# FPGA_POWER.net
KiCad netlist of a schematic drawn in Altium Designer
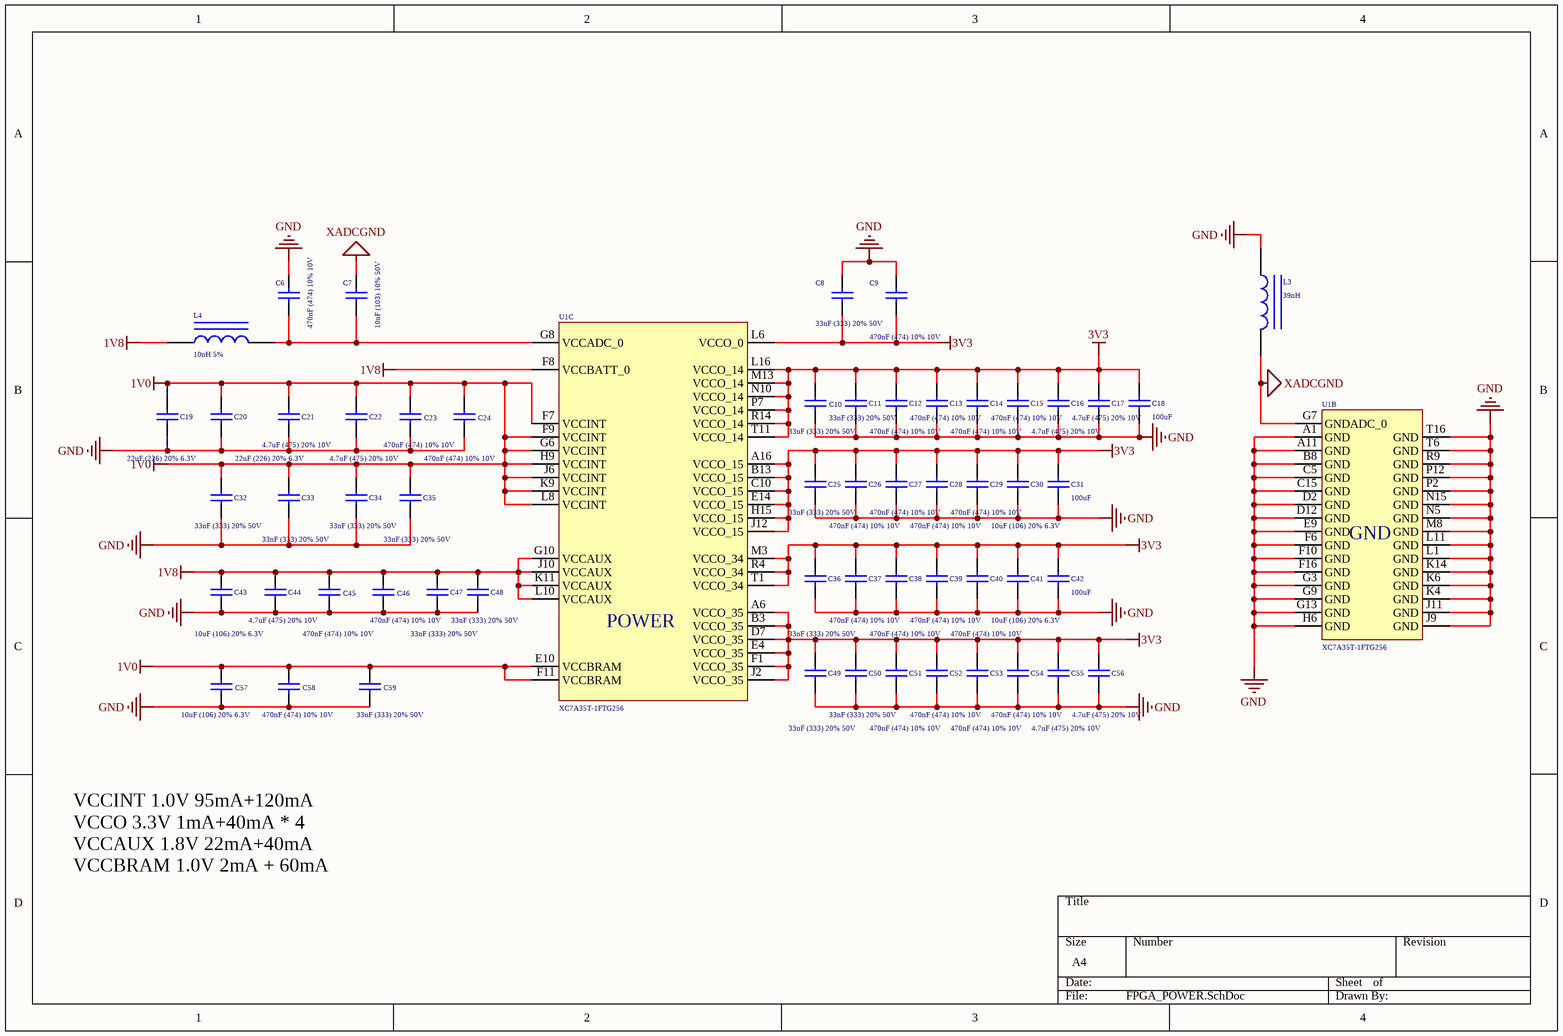
[diagram p0: FPGA_POWER.SchDoc]

(export (version "E")
  (design (tool "Eeschema 10.0.6"))
  (components
    (comp (ref "C6")
      (value "470nF (474) 10% 10V")
      (footprint "0402_C")
      (description "贴片电容")
      (libsource (lib "Cap") (part "0402 470nF (474) 10% 10V"))
    )
    (comp (ref "C7")
      (value "10nF (103) 10% 50V")
      (footprint "0402_C")
      (description "贴片电容")
      (libsource (lib "Cap") (part "0402 10nF (103) 10% 50V"))
    )
    (comp (ref "C8")
      (value "33nF (333) 20% 50V")
      (footprint "0402_C")
      (description "贴片电容")
      (libsource (lib "Cap") (part "0402 33nF (333) 20% 50V"))
    )
    (comp (ref "C9")
      (value "470nF (474) 10% 10V")
      (footprint "0402_C")
      (description "贴片电容")
      (libsource (lib "Cap") (part "0402 470nF (474) 10% 10V"))
    )
    (comp (ref "C10")
      (value "33nF (333) 20% 50V")
      (footprint "0402_C")
      (description "贴片电容")
      (libsource (lib "Cap") (part "0402 33nF (333) 20% 50V"))
    )
    (comp (ref "C11")
      (value "33nF (333) 20% 50V")
      (footprint "0402_C")
      (description "贴片电容")
      (libsource (lib "Cap") (part "0402 33nF (333) 20% 50V"))
    )
    (comp (ref "C12")
      (value "470nF (474) 10% 10V")
      (footprint "0402_C")
      (description "贴片电容")
      (libsource (lib "Cap") (part "0402 470nF (474) 10% 10V"))
    )
    (comp (ref "C13")
      (value "470nF (474) 10% 10V")
      (footprint "0402_C")
      (description "贴片电容")
      (libsource (lib "Cap") (part "0402 470nF (474) 10% 10V"))
    )
    (comp (ref "C14")
      (value "470nF (474) 10% 10V")
      (footprint "0402_C")
      (description "贴片电容")
      (libsource (lib "Cap") (part "0402 470nF (474) 10% 10V"))
    )
    (comp (ref "C15")
      (value "470nF (474) 10% 10V")
      (footprint "0402_C")
      (description "贴片电容")
      (libsource (lib "Cap") (part "0402 470nF (474) 10% 10V"))
    )
    (comp (ref "C16")
      (value "4.7uF (475) 20% 10V")
      (footprint "0402_C")
      (description "贴片电容")
      (libsource (lib "Cap") (part "0402 4.7uF (475) 20% 10V"))
    )
    (comp (ref "C17")
      (value "4.7uF (475) 20% 10V")
      (footprint "0402_C")
      (description "贴片电容")
      (libsource (lib "Cap") (part "0402 4.7uF (475) 20% 10V"))
    )
    (comp (ref "C18")
      (value "100uF")
      (footprint "LC-1206")
      (description "贴片电容")
      (fields (field (name "Comment") "Cap") (field (name "PUBLISHER") "Altium Limited"))
      (libsource (lib "Sparks") (part "Cap"))
    )
    (comp (ref "C19")
      (value "22uF (226) 20% 6.3V")
      (footprint "0603_C")
      (description "贴片电容")
      (libsource (lib "Miscellaneous Devices LC") (part "0603 22uF (226) 20% 6.3V"))
    )
    (comp (ref "C20")
      (value "22uF (226) 20% 6.3V")
      (footprint "0603_C")
      (description "贴片电容")
      (libsource (lib "Miscellaneous Devices LC") (part "0603 22uF (226) 20% 6.3V"))
    )
    (comp (ref "C21")
      (value "4.7uF (475) 20% 10V")
      (footprint "0402_C")
      (description "贴片电容")
      (libsource (lib "Cap") (part "0402 4.7uF (475) 20% 10V"))
    )
    (comp (ref "C22")
      (value "4.7uF (475) 20% 10V")
      (footprint "0402_C")
      (description "贴片电容")
      (libsource (lib "Cap") (part "0402 4.7uF (475) 20% 10V"))
    )
    (comp (ref "C23")
      (value "470nF (474) 10% 10V")
      (footprint "0402_C")
      (description "贴片电容")
      (libsource (lib "Cap") (part "0402 470nF (474) 10% 10V"))
    )
    (comp (ref "C24")
      (value "470nF (474) 10% 10V")
      (footprint "0402_C")
      (description "贴片电容")
      (libsource (lib "Cap") (part "0402 470nF (474) 10% 10V"))
    )
    (comp (ref "C25")
      (value "33nF (333) 20% 50V")
      (footprint "0402_C")
      (description "贴片电容")
      (libsource (lib "Cap") (part "0402 33nF (333) 20% 50V"))
    )
    (comp (ref "C26")
      (value "470nF (474) 10% 10V")
      (footprint "0402_C")
      (description "贴片电容")
      (libsource (lib "Cap") (part "0402 470nF (474) 10% 10V"))
    )
    (comp (ref "C27")
      (value "470nF (474) 10% 10V")
      (footprint "0402_C")
      (description "贴片电容")
      (libsource (lib "Cap") (part "0402 470nF (474) 10% 10V"))
    )
    (comp (ref "C28")
      (value "470nF (474) 10% 10V")
      (footprint "0402_C")
      (description "贴片电容")
      (libsource (lib "Cap") (part "0402 470nF (474) 10% 10V"))
    )
    (comp (ref "C29")
      (value "470nF (474) 10% 10V")
      (footprint "0402_C")
      (description "贴片电容")
      (libsource (lib "Cap") (part "0402 470nF (474) 10% 10V"))
    )
    (comp (ref "C30")
      (value "10uF (106) 20% 6.3V")
      (footprint "0402_C")
      (description "贴片电容")
      (libsource (lib "Cap") (part "0402 10uF (106) 20% 6.3V"))
    )
    (comp (ref "C31")
      (value "100uF")
      (footprint "LC-1206")
      (description "贴片电容")
      (fields (field (name "Comment") "Cap") (field (name "PUBLISHER") "Altium Limited"))
      (libsource (lib "Sparks") (part "Cap"))
    )
    (comp (ref "C32")
      (value "33nF (333) 20% 50V")
      (footprint "0402_C")
      (description "贴片电容")
      (libsource (lib "Cap") (part "0402 33nF (333) 20% 50V"))
    )
    (comp (ref "C33")
      (value "33nF (333) 20% 50V")
      (footprint "0402_C")
      (description "贴片电容")
      (libsource (lib "Cap") (part "0402 33nF (333) 20% 50V"))
    )
    (comp (ref "C34")
      (value "33nF (333) 20% 50V")
      (footprint "0402_C")
      (description "贴片电容")
      (libsource (lib "Cap") (part "0402 33nF (333) 20% 50V"))
    )
    (comp (ref "C35")
      (value "33nF (333) 20% 50V")
      (footprint "0402_C")
      (description "贴片电容")
      (libsource (lib "Cap") (part "0402 33nF (333) 20% 50V"))
    )
    (comp (ref "C36")
      (value "33nF (333) 20% 50V")
      (footprint "0402_C")
      (description "贴片电容")
      (libsource (lib "Cap") (part "0402 33nF (333) 20% 50V"))
    )
    (comp (ref "C37")
      (value "470nF (474) 10% 10V")
      (footprint "0402_C")
      (description "贴片电容")
      (libsource (lib "Cap") (part "0402 470nF (474) 10% 10V"))
    )
    (comp (ref "C38")
      (value "470nF (474) 10% 10V")
      (footprint "0402_C")
      (description "贴片电容")
      (libsource (lib "Cap") (part "0402 470nF (474) 10% 10V"))
    )
    (comp (ref "C39")
      (value "470nF (474) 10% 10V")
      (footprint "0402_C")
      (description "贴片电容")
      (libsource (lib "Cap") (part "0402 470nF (474) 10% 10V"))
    )
    (comp (ref "C40")
      (value "470nF (474) 10% 10V")
      (footprint "0402_C")
      (description "贴片电容")
      (libsource (lib "Cap") (part "0402 470nF (474) 10% 10V"))
    )
    (comp (ref "C41")
      (value "10uF (106) 20% 6.3V")
      (footprint "0402_C")
      (description "贴片电容")
      (libsource (lib "Cap") (part "0402 10uF (106) 20% 6.3V"))
    )
    (comp (ref "C42")
      (value "100uF")
      (footprint "LC-1206")
      (description "贴片电容")
      (fields (field (name "Comment") "Cap") (field (name "PUBLISHER") "Altium Limited"))
      (libsource (lib "Sparks") (part "Cap"))
    )
    (comp (ref "C43")
      (value "10uF (106) 20% 6.3V")
      (footprint "0402_C")
      (description "贴片电容")
      (libsource (lib "Cap") (part "0402 10uF (106) 20% 6.3V"))
    )
    (comp (ref "C44")
      (value "4.7uF (475) 20% 10V")
      (footprint "0402_C")
      (description "贴片电容")
      (libsource (lib "Cap") (part "0402 4.7uF (475) 20% 10V"))
    )
    (comp (ref "C45")
      (value "470nF (474) 10% 10V")
      (footprint "0402_C")
      (description "贴片电容")
      (libsource (lib "Cap") (part "0402 470nF (474) 10% 10V"))
    )
    (comp (ref "C46")
      (value "470nF (474) 10% 10V")
      (footprint "0402_C")
      (description "贴片电容")
      (libsource (lib "Cap") (part "0402 470nF (474) 10% 10V"))
    )
    (comp (ref "C47")
      (value "33nF (333) 20% 50V")
      (footprint "0402_C")
      (description "贴片电容")
      (libsource (lib "Cap") (part "0402 33nF (333) 20% 50V"))
    )
    (comp (ref "C48")
      (value "33nF (333) 20% 50V")
      (footprint "0402_C")
      (description "贴片电容")
      (libsource (lib "Cap") (part "0402 33nF (333) 20% 50V"))
    )
    (comp (ref "C49")
      (value "33nF (333) 20% 50V")
      (footprint "0402_C")
      (description "贴片电容")
      (libsource (lib "Cap") (part "0402 33nF (333) 20% 50V"))
    )
    (comp (ref "C50")
      (value "33nF (333) 20% 50V")
      (footprint "0402_C")
      (description "贴片电容")
      (libsource (lib "Cap") (part "0402 33nF (333) 20% 50V"))
    )
    (comp (ref "C51")
      (value "470nF (474) 10% 10V")
      (footprint "0402_C")
      (description "贴片电容")
      (libsource (lib "Cap") (part "0402 470nF (474) 10% 10V"))
    )
    (comp (ref "C52")
      (value "470nF (474) 10% 10V")
      (footprint "0402_C")
      (description "贴片电容")
      (libsource (lib "Cap") (part "0402 470nF (474) 10% 10V"))
    )
    (comp (ref "C53")
      (value "470nF (474) 10% 10V")
      (footprint "0402_C")
      (description "贴片电容")
      (libsource (lib "Cap") (part "0402 470nF (474) 10% 10V"))
    )
    (comp (ref "C54")
      (value "470nF (474) 10% 10V")
      (footprint "0402_C")
      (description "贴片电容")
      (libsource (lib "Cap") (part "0402 470nF (474) 10% 10V"))
    )
    (comp (ref "C55")
      (value "4.7uF (475) 20% 10V")
      (footprint "0402_C")
      (description "贴片电容")
      (libsource (lib "Cap") (part "0402 4.7uF (475) 20% 10V"))
    )
    (comp (ref "C56")
      (value "4.7uF (475) 20% 10V")
      (footprint "0402_C")
      (description "贴片电容")
      (libsource (lib "Cap") (part "0402 4.7uF (475) 20% 10V"))
    )
    (comp (ref "C57")
      (value "10uF (106) 20% 6.3V")
      (footprint "0402_C")
      (description "贴片电容")
      (libsource (lib "Cap") (part "0402 10uF (106) 20% 6.3V"))
    )
    (comp (ref "C58")
      (value "470nF (474) 10% 10V")
      (footprint "0402_C")
      (description "贴片电容")
      (libsource (lib "Cap") (part "0402 470nF (474) 10% 10V"))
    )
    (comp (ref "C59")
      (value "33nF (333) 20% 50V")
      (footprint "0402_C")
      (description "贴片电容")
      (libsource (lib "Cap") (part "0402 33nF (333) 20% 50V"))
    )
    (comp (ref "L3")
      (value "39nH")
      (footprint "0402_L")
      (description "贴片电感")
      (libsource (lib "IUD") (part "0402 39nH"))
    )
    (comp (ref "L4")
      (value "10nH 5%")
      (footprint "0402_L")
      (description "贴片电感")
      (libsource (lib "IUD") (part "0402 10nH 5%"))
    )
    (comp (ref "U1")
      (value "XC7A35T-1FTG256")
      (footprint "BGA100P9X9-81A")
      (libsource (lib "Schlib") (part "XC7A35T-1FTG256"))
    )
  )
  (nets
    (net (code "1") (name "1V0") (class "Default")
      (node (ref "C19") (pin "2") (pinfunction "2_2") (pintype "passive"))
      (node (ref "C20") (pin "2") (pinfunction "2_2") (pintype "passive"))
      (node (ref "C21") (pin "2") (pinfunction "2_2") (pintype "passive"))
      (node (ref "C22") (pin "2") (pinfunction "2_2") (pintype "passive"))
      (node (ref "C23") (pin "2") (pinfunction "2_2") (pintype "passive"))
      (node (ref "C24") (pin "2") (pinfunction "2_2") (pintype "passive"))
      (node (ref "C32") (pin "2") (pinfunction "2_2") (pintype "passive"))
      (node (ref "C33") (pin "2") (pinfunction "2_2") (pintype "passive"))
      (node (ref "C34") (pin "2") (pinfunction "2_2") (pintype "passive"))
      (node (ref "C35") (pin "2") (pinfunction "2_2") (pintype "passive"))
      (node (ref "C57") (pin "2") (pinfunction "2_2") (pintype "passive"))
      (node (ref "C58") (pin "2") (pinfunction "2_2") (pintype "passive"))
      (node (ref "C59") (pin "2") (pinfunction "2_2") (pintype "passive"))
      (node (ref "U1") (pin "E10") (pinfunction "VCCBRAM_E10") (pintype "passive"))
      (node (ref "U1") (pin "F11") (pinfunction "VCCBRAM_F11") (pintype "passive"))
      (node (ref "U1") (pin "F7") (pinfunction "VCCINT_F7") (pintype "passive"))
      (node (ref "U1") (pin "F9") (pinfunction "VCCINT_F9") (pintype "passive"))
      (node (ref "U1") (pin "G6") (pinfunction "VCCINT_G6") (pintype "passive"))
      (node (ref "U1") (pin "H9") (pinfunction "VCCINT_H9") (pintype "passive"))
      (node (ref "U1") (pin "J6") (pinfunction "VCCINT_J6") (pintype "passive"))
      (node (ref "U1") (pin "K9") (pinfunction "VCCINT_K9") (pintype "passive"))
      (node (ref "U1") (pin "L8") (pinfunction "VCCINT_L8") (pintype "passive"))
    )
    (net (code "2") (name "1V8") (class "Default")
      (node (ref "C43") (pin "2") (pinfunction "2_2") (pintype "passive"))
      (node (ref "C44") (pin "2") (pinfunction "2_2") (pintype "passive"))
      (node (ref "C45") (pin "2") (pinfunction "2_2") (pintype "passive"))
      (node (ref "C46") (pin "2") (pinfunction "2_2") (pintype "passive"))
      (node (ref "C47") (pin "2") (pinfunction "2_2") (pintype "passive"))
      (node (ref "C48") (pin "2") (pinfunction "2_2") (pintype "passive"))
      (node (ref "L4") (pin "1") (pinfunction "1_1") (pintype "passive"))
      (node (ref "U1") (pin "F8") (pinfunction "VCCBATT_0_F8") (pintype "passive"))
      (node (ref "U1") (pin "G10") (pinfunction "VCCAUX_G10") (pintype "passive"))
      (node (ref "U1") (pin "J10") (pinfunction "VCCAUX_J10") (pintype "passive"))
      (node (ref "U1") (pin "K11") (pinfunction "VCCAUX_K11") (pintype "passive"))
      (node (ref "U1") (pin "L10") (pinfunction "VCCAUX_L10") (pintype "passive"))
    )
    (net (code "3") (name "3V3") (class "Default")
      (node (ref "C10") (pin "2") (pinfunction "2_2") (pintype "passive"))
      (node (ref "C11") (pin "2") (pinfunction "2_2") (pintype "passive"))
      (node (ref "C12") (pin "2") (pinfunction "2_2") (pintype "passive"))
      (node (ref "C13") (pin "2") (pinfunction "2_2") (pintype "passive"))
      (node (ref "C14") (pin "2") (pinfunction "2_2") (pintype "passive"))
      (node (ref "C15") (pin "2") (pinfunction "2_2") (pintype "passive"))
      (node (ref "C16") (pin "2") (pinfunction "2_2") (pintype "passive"))
      (node (ref "C17") (pin "2") (pinfunction "2_2") (pintype "passive"))
      (node (ref "C18") (pin "2") (pinfunction "2_2") (pintype "passive"))
      (node (ref "C25") (pin "2") (pinfunction "2_2") (pintype "passive"))
      (node (ref "C26") (pin "2") (pinfunction "2_2") (pintype "passive"))
      (node (ref "C27") (pin "2") (pinfunction "2_2") (pintype "passive"))
      (node (ref "C28") (pin "2") (pinfunction "2_2") (pintype "passive"))
      (node (ref "C29") (pin "2") (pinfunction "2_2") (pintype "passive"))
      (node (ref "C30") (pin "2") (pinfunction "2_2") (pintype "passive"))
      (node (ref "C31") (pin "2") (pinfunction "2_2") (pintype "passive"))
      (node (ref "C36") (pin "2") (pinfunction "2_2") (pintype "passive"))
      (node (ref "C37") (pin "2") (pinfunction "2_2") (pintype "passive"))
      (node (ref "C38") (pin "2") (pinfunction "2_2") (pintype "passive"))
      (node (ref "C39") (pin "2") (pinfunction "2_2") (pintype "passive"))
      (node (ref "C40") (pin "2") (pinfunction "2_2") (pintype "passive"))
      (node (ref "C41") (pin "2") (pinfunction "2_2") (pintype "passive"))
      (node (ref "C42") (pin "2") (pinfunction "2_2") (pintype "passive"))
      (node (ref "C49") (pin "2") (pinfunction "2_2") (pintype "passive"))
      (node (ref "C50") (pin "2") (pinfunction "2_2") (pintype "passive"))
      (node (ref "C51") (pin "2") (pinfunction "2_2") (pintype "passive"))
      (node (ref "C52") (pin "2") (pinfunction "2_2") (pintype "passive"))
      (node (ref "C53") (pin "2") (pinfunction "2_2") (pintype "passive"))
      (node (ref "C54") (pin "2") (pinfunction "2_2") (pintype "passive"))
      (node (ref "C55") (pin "2") (pinfunction "2_2") (pintype "passive"))
      (node (ref "C56") (pin "2") (pinfunction "2_2") (pintype "passive"))
      (node (ref "C8") (pin "1") (pinfunction "1_1") (pintype "passive"))
      (node (ref "C9") (pin "1") (pinfunction "1_1") (pintype "passive"))
      (node (ref "U1") (pin "A16") (pinfunction "VCCO_15_A16") (pintype "passive"))
      (node (ref "U1") (pin "A6") (pinfunction "VCCO_35_A6") (pintype "passive"))
      (node (ref "U1") (pin "B13") (pinfunction "VCCO_15_B13") (pintype "passive"))
      (node (ref "U1") (pin "B3") (pinfunction "VCCO_35_B3") (pintype "passive"))
      (node (ref "U1") (pin "C10") (pinfunction "VCCO_15_C10") (pintype "passive"))
      (node (ref "U1") (pin "D7") (pinfunction "VCCO_35_D7") (pintype "passive"))
      (node (ref "U1") (pin "E14") (pinfunction "VCCO_15_E14") (pintype "passive"))
      (node (ref "U1") (pin "E4") (pinfunction "VCCO_35_E4") (pintype "passive"))
      (node (ref "U1") (pin "F1") (pinfunction "VCCO_35_F1") (pintype "passive"))
      (node (ref "U1") (pin "H15") (pinfunction "VCCO_15_H15") (pintype "passive"))
      (node (ref "U1") (pin "J12") (pinfunction "VCCO_15_J12") (pintype "passive"))
      (node (ref "U1") (pin "J2") (pinfunction "VCCO_35_J2") (pintype "passive"))
      (node (ref "U1") (pin "L16") (pinfunction "VCCO_14_L16") (pintype "passive"))
      (node (ref "U1") (pin "L6") (pinfunction "VCCO_0_L6") (pintype "passive"))
      (node (ref "U1") (pin "M13") (pinfunction "VCCO_14_M13") (pintype "passive"))
      (node (ref "U1") (pin "M3") (pinfunction "VCCO_34_M3") (pintype "passive"))
      (node (ref "U1") (pin "N10") (pinfunction "VCCO_14_N10") (pintype "passive"))
      (node (ref "U1") (pin "P7") (pinfunction "VCCO_14_P7") (pintype "passive"))
      (node (ref "U1") (pin "R14") (pinfunction "VCCO_14_R14") (pintype "passive"))
      (node (ref "U1") (pin "R4") (pinfunction "VCCO_34_R4") (pintype "passive"))
      (node (ref "U1") (pin "T1") (pinfunction "VCCO_34_T1") (pintype "passive"))
      (node (ref "U1") (pin "T11") (pinfunction "VCCO_14_T11") (pintype "passive"))
    )
    (net (code "4") (name "GND") (class "Default")
      (node (ref "C10") (pin "1") (pinfunction "1_1") (pintype "passive"))
      (node (ref "C11") (pin "1") (pinfunction "1_1") (pintype "passive"))
      (node (ref "C12") (pin "1") (pinfunction "1_1") (pintype "passive"))
      (node (ref "C13") (pin "1") (pinfunction "1_1") (pintype "passive"))
      (node (ref "C14") (pin "1") (pinfunction "1_1") (pintype "passive"))
      (node (ref "C15") (pin "1") (pinfunction "1_1") (pintype "passive"))
      (node (ref "C16") (pin "1") (pinfunction "1_1") (pintype "passive"))
      (node (ref "C17") (pin "1") (pinfunction "1_1") (pintype "passive"))
      (node (ref "C18") (pin "1") (pinfunction "1_1") (pintype "passive"))
      (node (ref "C19") (pin "1") (pinfunction "1_1") (pintype "passive"))
      (node (ref "C20") (pin "1") (pinfunction "1_1") (pintype "passive"))
      (node (ref "C21") (pin "1") (pinfunction "1_1") (pintype "passive"))
      (node (ref "C22") (pin "1") (pinfunction "1_1") (pintype "passive"))
      (node (ref "C23") (pin "1") (pinfunction "1_1") (pintype "passive"))
      (node (ref "C24") (pin "1") (pinfunction "1_1") (pintype "passive"))
      (node (ref "C25") (pin "1") (pinfunction "1_1") (pintype "passive"))
      (node (ref "C26") (pin "1") (pinfunction "1_1") (pintype "passive"))
      (node (ref "C27") (pin "1") (pinfunction "1_1") (pintype "passive"))
      (node (ref "C28") (pin "1") (pinfunction "1_1") (pintype "passive"))
      (node (ref "C29") (pin "1") (pinfunction "1_1") (pintype "passive"))
      (node (ref "C30") (pin "1") (pinfunction "1_1") (pintype "passive"))
      (node (ref "C31") (pin "1") (pinfunction "1_1") (pintype "passive"))
      (node (ref "C32") (pin "1") (pinfunction "1_1") (pintype "passive"))
      (node (ref "C33") (pin "1") (pinfunction "1_1") (pintype "passive"))
      (node (ref "C34") (pin "1") (pinfunction "1_1") (pintype "passive"))
      (node (ref "C35") (pin "1") (pinfunction "1_1") (pintype "passive"))
      (node (ref "C36") (pin "1") (pinfunction "1_1") (pintype "passive"))
      (node (ref "C37") (pin "1") (pinfunction "1_1") (pintype "passive"))
      (node (ref "C38") (pin "1") (pinfunction "1_1") (pintype "passive"))
      (node (ref "C39") (pin "1") (pinfunction "1_1") (pintype "passive"))
      (node (ref "C40") (pin "1") (pinfunction "1_1") (pintype "passive"))
      (node (ref "C41") (pin "1") (pinfunction "1_1") (pintype "passive"))
      (node (ref "C42") (pin "1") (pinfunction "1_1") (pintype "passive"))
      (node (ref "C43") (pin "1") (pinfunction "1_1") (pintype "passive"))
      (node (ref "C44") (pin "1") (pinfunction "1_1") (pintype "passive"))
      (node (ref "C45") (pin "1") (pinfunction "1_1") (pintype "passive"))
      (node (ref "C46") (pin "1") (pinfunction "1_1") (pintype "passive"))
      (node (ref "C47") (pin "1") (pinfunction "1_1") (pintype "passive"))
      (node (ref "C48") (pin "1") (pinfunction "1_1") (pintype "passive"))
      (node (ref "C49") (pin "1") (pinfunction "1_1") (pintype "passive"))
      (node (ref "C50") (pin "1") (pinfunction "1_1") (pintype "passive"))
      (node (ref "C51") (pin "1") (pinfunction "1_1") (pintype "passive"))
      (node (ref "C52") (pin "1") (pinfunction "1_1") (pintype "passive"))
      (node (ref "C53") (pin "1") (pinfunction "1_1") (pintype "passive"))
      (node (ref "C54") (pin "1") (pinfunction "1_1") (pintype "passive"))
      (node (ref "C55") (pin "1") (pinfunction "1_1") (pintype "passive"))
      (node (ref "C56") (pin "1") (pinfunction "1_1") (pintype "passive"))
      (node (ref "C57") (pin "1") (pinfunction "1_1") (pintype "passive"))
      (node (ref "C58") (pin "1") (pinfunction "1_1") (pintype "passive"))
      (node (ref "C59") (pin "1") (pinfunction "1_1") (pintype "passive"))
      (node (ref "C6") (pin "2") (pinfunction "2_2") (pintype "passive"))
      (node (ref "C8") (pin "2") (pinfunction "2_2") (pintype "passive"))
      (node (ref "C9") (pin "2") (pinfunction "2_2") (pintype "passive"))
      (node (ref "L3") (pin "1") (pinfunction "1_1") (pintype "passive"))
      (node (ref "U1") (pin "A1") (pinfunction "GND_A1") (pintype "passive"))
      (node (ref "U1") (pin "A11") (pinfunction "GND_A11") (pintype "passive"))
      (node (ref "U1") (pin "B8") (pinfunction "GND_B8") (pintype "passive"))
      (node (ref "U1") (pin "C15") (pinfunction "GND_C15") (pintype "passive"))
      (node (ref "U1") (pin "C5") (pinfunction "GND_C5") (pintype "passive"))
      (node (ref "U1") (pin "D12") (pinfunction "GND_D12") (pintype "passive"))
      (node (ref "U1") (pin "D2") (pinfunction "GND_D2") (pintype "passive"))
      (node (ref "U1") (pin "E9") (pinfunction "GND_E9") (pintype "passive"))
      (node (ref "U1") (pin "F10") (pinfunction "GND_F10") (pintype "passive"))
      (node (ref "U1") (pin "F16") (pinfunction "GND_F16") (pintype "passive"))
      (node (ref "U1") (pin "F6") (pinfunction "GND_F6") (pintype "passive"))
      (node (ref "U1") (pin "G13") (pinfunction "GND_G13") (pintype "passive"))
      (node (ref "U1") (pin "G3") (pinfunction "GND_G3") (pintype "passive"))
      (node (ref "U1") (pin "G9") (pinfunction "GND_G9") (pintype "passive"))
      (node (ref "U1") (pin "H6") (pinfunction "GND_H6") (pintype "passive"))
      (node (ref "U1") (pin "J11") (pinfunction "GND_J11") (pintype "passive"))
      (node (ref "U1") (pin "J9") (pinfunction "GND_J9") (pintype "passive"))
      (node (ref "U1") (pin "K14") (pinfunction "GND_K14") (pintype "passive"))
      (node (ref "U1") (pin "K4") (pinfunction "GND_K4") (pintype "passive"))
      (node (ref "U1") (pin "K6") (pinfunction "GND_K6") (pintype "passive"))
      (node (ref "U1") (pin "L1") (pinfunction "GND_L1") (pintype "passive"))
      (node (ref "U1") (pin "L11") (pinfunction "GND_L11") (pintype "passive"))
      (node (ref "U1") (pin "M8") (pinfunction "GND_M8") (pintype "passive"))
      (node (ref "U1") (pin "N15") (pinfunction "GND_N15") (pintype "passive"))
      (node (ref "U1") (pin "N5") (pinfunction "GND_N5") (pintype "passive"))
      (node (ref "U1") (pin "P12") (pinfunction "GND_P12") (pintype "passive"))
      (node (ref "U1") (pin "P2") (pinfunction "GND_P2") (pintype "passive"))
      (node (ref "U1") (pin "R9") (pinfunction "GND_R9") (pintype "passive"))
      (node (ref "U1") (pin "T16") (pinfunction "GND_T16") (pintype "passive"))
      (node (ref "U1") (pin "T6") (pinfunction "GND_T6") (pintype "passive"))
    )
    (net (code "5") (name "Net-(U1C-VCCADC_0)") (class "Default")
      (node (ref "C6") (pin "1") (pinfunction "1_1") (pintype "passive"))
      (node (ref "C7") (pin "1") (pinfunction "1_1") (pintype "passive"))
      (node (ref "L4") (pin "2") (pinfunction "2_2") (pintype "passive"))
      (node (ref "U1") (pin "G8") (pinfunction "VCCADC_0_G8") (pintype "passive"))
    )
    (net (code "6") (name "XADCGND") (class "Default")
      (node (ref "C7") (pin "2") (pinfunction "2_2") (pintype "passive"))
      (node (ref "L3") (pin "2") (pinfunction "2_2") (pintype "passive"))
      (node (ref "U1") (pin "G7") (pinfunction "GNDADC_0_G7") (pintype "passive"))
    )
  )
)
